# Mechatronics_Pneumatic_controller.net
KiCad netlist of a schematic drawn in EAGLE
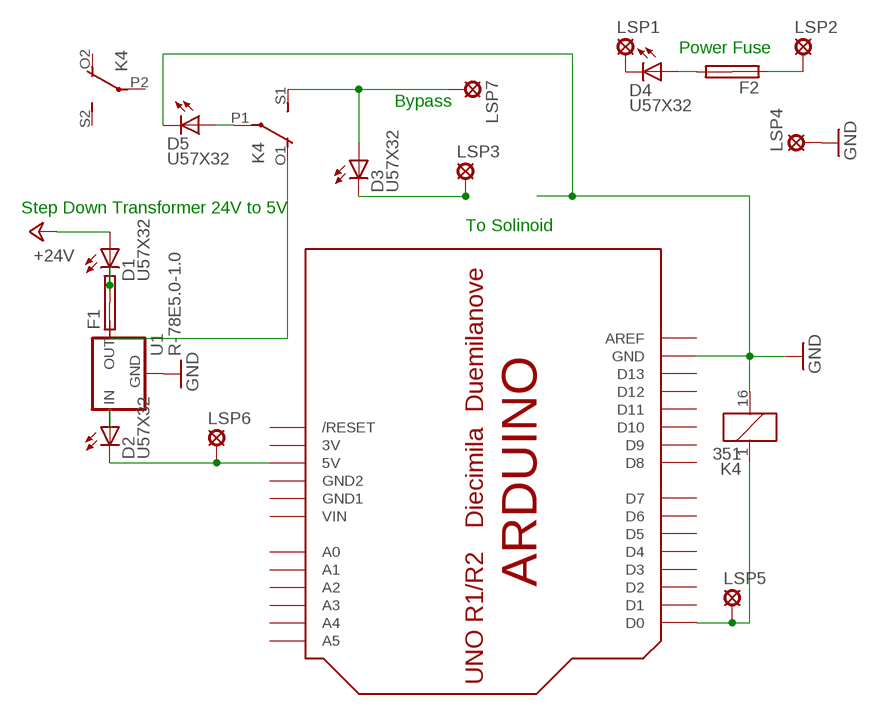
[diagram p0: schematic, sheet 1]

(export (version "E")
  (design (tool "Eeschema 10.0.6"))
  (components
    (comp (ref "D1")
      (value "U57X32")
      (footprint "eagle-import:U57X32")
      (libsource (lib "eagle-import") (part "U57X32"))
    )
    (comp (ref "D2")
      (value "U57X32")
      (footprint "eagle-import:U57X32")
      (libsource (lib "eagle-import") (part "U57X32"))
    )
    (comp (ref "D3")
      (value "U57X32")
      (footprint "eagle-import:U57X32")
      (libsource (lib "eagle-import") (part "U57X32"))
    )
    (comp (ref "D4")
      (value "U57X32")
      (footprint "eagle-import:U57X32")
      (libsource (lib "eagle-import") (part "U57X32"))
    )
    (comp (ref "D5")
      (value "U57X32")
      (footprint "eagle-import:U57X32")
      (libsource (lib "eagle-import") (part "U57X32"))
    )
    (comp (ref "F1")
      (value "SHK20L")
      (footprint "eagle-import:SHK20L")
      (libsource (lib "eagle-import") (part "SHK20L"))
    )
    (comp (ref "F2")
      (value "SHK20L")
      (footprint "eagle-import:SHK20L")
      (libsource (lib "eagle-import") (part "SHK20L"))
    )
    (comp (ref "K4")
      (value "351")
      (footprint "eagle-import:351")
      (libsource (lib "eagle-import") (part "351"))
    )
    (comp (ref "LSP1")
      (value "LSP10")
      (footprint "eagle-import:LSP10")
      (libsource (lib "eagle-import") (part "LSP10"))
    )
    (comp (ref "LSP2")
      (value "LSP10")
      (footprint "eagle-import:LSP10")
      (libsource (lib "eagle-import") (part "LSP10"))
    )
    (comp (ref "LSP3")
      (value "LSP10")
      (footprint "eagle-import:LSP10")
      (libsource (lib "eagle-import") (part "LSP10"))
    )
    (comp (ref "LSP4")
      (value "LSP10")
      (footprint "eagle-import:LSP10")
      (libsource (lib "eagle-import") (part "LSP10"))
    )
    (comp (ref "LSP5")
      (value "LSP10")
      (footprint "eagle-import:LSP10")
      (libsource (lib "eagle-import") (part "LSP10"))
    )
    (comp (ref "LSP6")
      (value "LSP10")
      (footprint "eagle-import:LSP10")
      (libsource (lib "eagle-import") (part "LSP10"))
    )
    (comp (ref "LSP7")
      (value "LSP10")
      (footprint "eagle-import:LSP10")
      (libsource (lib "eagle-import") (part "LSP10"))
    )
    (comp (ref "U$1")
      (value "ARDUINOUNO")
      (footprint "eagle-import:ARDUINO")
      (libsource (lib "eagle-import") (part "ARDUINOUNO"))
    )
    (comp (ref "U1")
      (value "R-78E5.0-1.0")
      (footprint "eagle-import:DC-DC_CONVERTER_78XX")
      (libsource (lib "eagle-import") (part "R-78E5.0-1.0"))
    )
  )
  (nets
    (net (code "1") (name "+24V") (class "Default")
      (node (ref "D1") (pin "A") (pinfunction "A_A") (pintype "passive"))
    )
    (net (code "2") (name "/3V") (class "Default")
      (node (ref "U$1") (pin "3V") (pinfunction "3V_3V") (pintype "power_in"))
    )
    (net (code "3") (name "/GND1") (class "Default")
      (node (ref "U$1") (pin "GND1") (pinfunction "GND1_GND1") (pintype "power_in"))
    )
    (net (code "4") (name "/GND2") (class "Default")
      (node (ref "U$1") (pin "GND2") (pinfunction "GND2_GND2") (pintype "power_in"))
    )
    (net (code "5") (name "/VIN") (class "Default")
      (node (ref "U$1") (pin "VIN") (pinfunction "VIN_VIN") (pintype "power_in"))
    )
    (net (code "6") (name "GND") (class "Default")
      (node (ref "D5") (pin "K") (pinfunction "C_K") (pintype "passive"))
      (node (ref "K4") (pin "16") (pinfunction "2_16") (pintype "passive"))
      (node (ref "LSP4") (pin "MP") (pinfunction "MP_MP") (pintype "passive"))
      (node (ref "U$1") (pin "GND") (pinfunction "GND_GND") (pintype "power_in"))
      (node (ref "U1") (pin "GND") (pinfunction "GND_GND") (pintype "input"))
    )
    (net (code "7") (name "Net-(D1-C)") (class "Default")
      (node (ref "D1") (pin "K") (pinfunction "C_K") (pintype "passive"))
      (node (ref "F1") (pin "2A") (pinfunction "2A_2A") (pintype "passive"))
      (node (ref "F1") (pin "2B") (pinfunction "2B_2B") (pintype "passive"))
    )
    (net (code "8") (name "Net-(D2-C)") (class "Default")
      (node (ref "D2") (pin "K") (pinfunction "C_K") (pintype "passive"))
      (node (ref "LSP6") (pin "MP") (pinfunction "MP_MP") (pintype "passive"))
      (node (ref "U$1") (pin "5V") (pinfunction "5V_5V") (pintype "power_in"))
    )
    (net (code "9") (name "Net-(D3-C)") (class "Default")
      (node (ref "D3") (pin "K") (pinfunction "C_K") (pintype "passive"))
      (node (ref "LSP3") (pin "MP") (pinfunction "MP_MP") (pintype "passive"))
    )
    (net (code "10") (name "Net-(D4-C)") (class "Default")
      (node (ref "D4") (pin "K") (pinfunction "C_K") (pintype "passive"))
      (node (ref "LSP1") (pin "MP") (pinfunction "MP_MP") (pintype "passive"))
    )
    (net (code "11") (name "Net-(D4-PadA)") (class "Default")
      (node (ref "D4") (pin "A") (pinfunction "A_A") (pintype "passive"))
      (node (ref "F2") (pin "2A") (pinfunction "2A_2A") (pintype "passive"))
    )
    (net (code "12") (name "Net-(F2-Pad1A)") (class "Default")
      (node (ref "F2") (pin "1A") (pinfunction "1A_1A") (pintype "passive"))
      (node (ref "LSP2") (pin "MP") (pinfunction "MP_MP") (pintype "passive"))
    )
    (net (code "13") (name "Net-(K4-Pad1)") (class "Default")
      (node (ref "K4") (pin "1") (pinfunction "1_1") (pintype "passive"))
      (node (ref "LSP5") (pin "MP") (pinfunction "MP_MP") (pintype "passive"))
      (node (ref "U$1") (pin "D0") (pinfunction "D0_D0") (pintype "bidirectional"))
    )
    (net (code "14") (name "Net-(K4B-O)") (class "Default")
      (node (ref "F1") (pin "1A") (pinfunction "1A_1A") (pintype "passive"))
      (node (ref "K4") (pin "O1") (pinfunction "O_O1") (pintype "passive"))
    )
    (net (code "15") (name "Net-(K4B-P)") (class "Default")
      (node (ref "D5") (pin "A") (pinfunction "A_A") (pintype "passive"))
      (node (ref "K4") (pin "P1") (pinfunction "P_P1") (pintype "passive"))
    )
    (net (code "16") (name "Net-(K4B-S)") (class "Default")
      (node (ref "D3") (pin "A") (pinfunction "A_A") (pintype "passive"))
      (node (ref "K4") (pin "S1") (pinfunction "S_S1") (pintype "passive"))
      (node (ref "LSP7") (pin "MP") (pinfunction "MP_MP") (pintype "passive"))
    )
    (net (code "17") (name "Net-(U1-IN)") (class "Default")
      (node (ref "D2") (pin "A") (pinfunction "A_A") (pintype "passive"))
      (node (ref "U1") (pin "VIN") (pinfunction "IN_VIN") (pintype "input"))
    )
    (net (code "18") (name "Net-(U1-OUT)") (class "Default")
      (node (ref "F1") (pin "1B") (pinfunction "1B_1B") (pintype "passive"))
      (node (ref "U1") (pin "VOUT") (pinfunction "OUT_VOUT") (pintype "passive"))
    )
    (net (code "19") (name "unconnected-(F2-Pad1B)") (class "Default")
      (node (ref "F2") (pin "1B") (pinfunction "1B_1B") (pintype "passive"))
    )
    (net (code "20") (name "unconnected-(F2-Pad2B)") (class "Default")
      (node (ref "F2") (pin "2B") (pinfunction "2B_2B") (pintype "passive"))
    )
    (net (code "21") (name "unconnected-(K4C-O-PadO2)") (class "Default")
      (node (ref "K4") (pin "O2") (pinfunction "O_O2") (pintype "passive"))
    )
    (net (code "22") (name "unconnected-(K4C-P-PadP2)") (class "Default")
      (node (ref "K4") (pin "P2") (pinfunction "P_P2") (pintype "passive"))
    )
    (net (code "23") (name "unconnected-(K4C-S-PadS2)") (class "Default")
      (node (ref "K4") (pin "S2") (pinfunction "S_S2") (pintype "passive"))
    )
    (net (code "24") (name "unconnected-(U$1-PadA0)") (class "Default")
      (node (ref "U$1") (pin "A0") (pinfunction "A0_A0") (pintype "bidirectional"))
    )
    (net (code "25") (name "unconnected-(U$1-PadA1)") (class "Default")
      (node (ref "U$1") (pin "A1") (pinfunction "A1_A1") (pintype "bidirectional"))
    )
    (net (code "26") (name "unconnected-(U$1-PadA2)") (class "Default")
      (node (ref "U$1") (pin "A2") (pinfunction "A2_A2") (pintype "bidirectional"))
    )
    (net (code "27") (name "unconnected-(U$1-PadA3)") (class "Default")
      (node (ref "U$1") (pin "A3") (pinfunction "A3_A3") (pintype "bidirectional"))
    )
    (net (code "28") (name "unconnected-(U$1-PadA4)") (class "Default")
      (node (ref "U$1") (pin "A4") (pinfunction "A4_A4") (pintype "bidirectional"))
    )
    (net (code "29") (name "unconnected-(U$1-PadA5)") (class "Default")
      (node (ref "U$1") (pin "A5") (pinfunction "A5_A5") (pintype "bidirectional"))
    )
    (net (code "30") (name "unconnected-(U$1-PadAREF)") (class "Default")
      (node (ref "U$1") (pin "AREF") (pinfunction "AREF_AREF") (pintype "bidirectional"))
    )
    (net (code "31") (name "unconnected-(U$1-PadD1)") (class "Default")
      (node (ref "U$1") (pin "D1") (pinfunction "D1_D1") (pintype "bidirectional"))
    )
    (net (code "32") (name "unconnected-(U$1-PadD2)") (class "Default")
      (node (ref "U$1") (pin "D2") (pinfunction "D2_D2") (pintype "bidirectional"))
    )
    (net (code "33") (name "unconnected-(U$1-PadD3)") (class "Default")
      (node (ref "U$1") (pin "D3") (pinfunction "D3_D3") (pintype "bidirectional"))
    )
    (net (code "34") (name "unconnected-(U$1-PadD4)") (class "Default")
      (node (ref "U$1") (pin "D4") (pinfunction "D4_D4") (pintype "bidirectional"))
    )
    (net (code "35") (name "unconnected-(U$1-PadD5)") (class "Default")
      (node (ref "U$1") (pin "D5") (pinfunction "D5_D5") (pintype "bidirectional"))
    )
    (net (code "36") (name "unconnected-(U$1-PadD6)") (class "Default")
      (node (ref "U$1") (pin "D6") (pinfunction "D6_D6") (pintype "bidirectional"))
    )
    (net (code "37") (name "unconnected-(U$1-PadD7)") (class "Default")
      (node (ref "U$1") (pin "D7") (pinfunction "D7_D7") (pintype "bidirectional"))
    )
    (net (code "38") (name "unconnected-(U$1-PadD8)") (class "Default")
      (node (ref "U$1") (pin "D8") (pinfunction "D8_D8") (pintype "bidirectional"))
    )
    (net (code "39") (name "unconnected-(U$1-PadD9)") (class "Default")
      (node (ref "U$1") (pin "D9") (pinfunction "D9_D9") (pintype "bidirectional"))
    )
    (net (code "40") (name "unconnected-(U$1-PadD10)") (class "Default")
      (node (ref "U$1") (pin "D10") (pinfunction "D10_D10") (pintype "bidirectional"))
    )
    (net (code "41") (name "unconnected-(U$1-PadD11)") (class "Default")
      (node (ref "U$1") (pin "D11") (pinfunction "D11_D11") (pintype "bidirectional"))
    )
    (net (code "42") (name "unconnected-(U$1-PadD12)") (class "Default")
      (node (ref "U$1") (pin "D12") (pinfunction "D12_D12") (pintype "bidirectional"))
    )
    (net (code "43") (name "unconnected-(U$1-PadD13)") (class "Default")
      (node (ref "U$1") (pin "D13") (pinfunction "D13_D13") (pintype "bidirectional"))
    )
    (net (code "44") (name "unconnected-(U$1-{slash}RESET-PadRESET)") (class "Default")
      (node (ref "U$1") (pin "RESET") (pinfunction "/RESET_RESET") (pintype "bidirectional"))
    )
  )
)
